# DummyLoadAddOn.net
KiCad netlist of a schematic drawn in Altium Designer
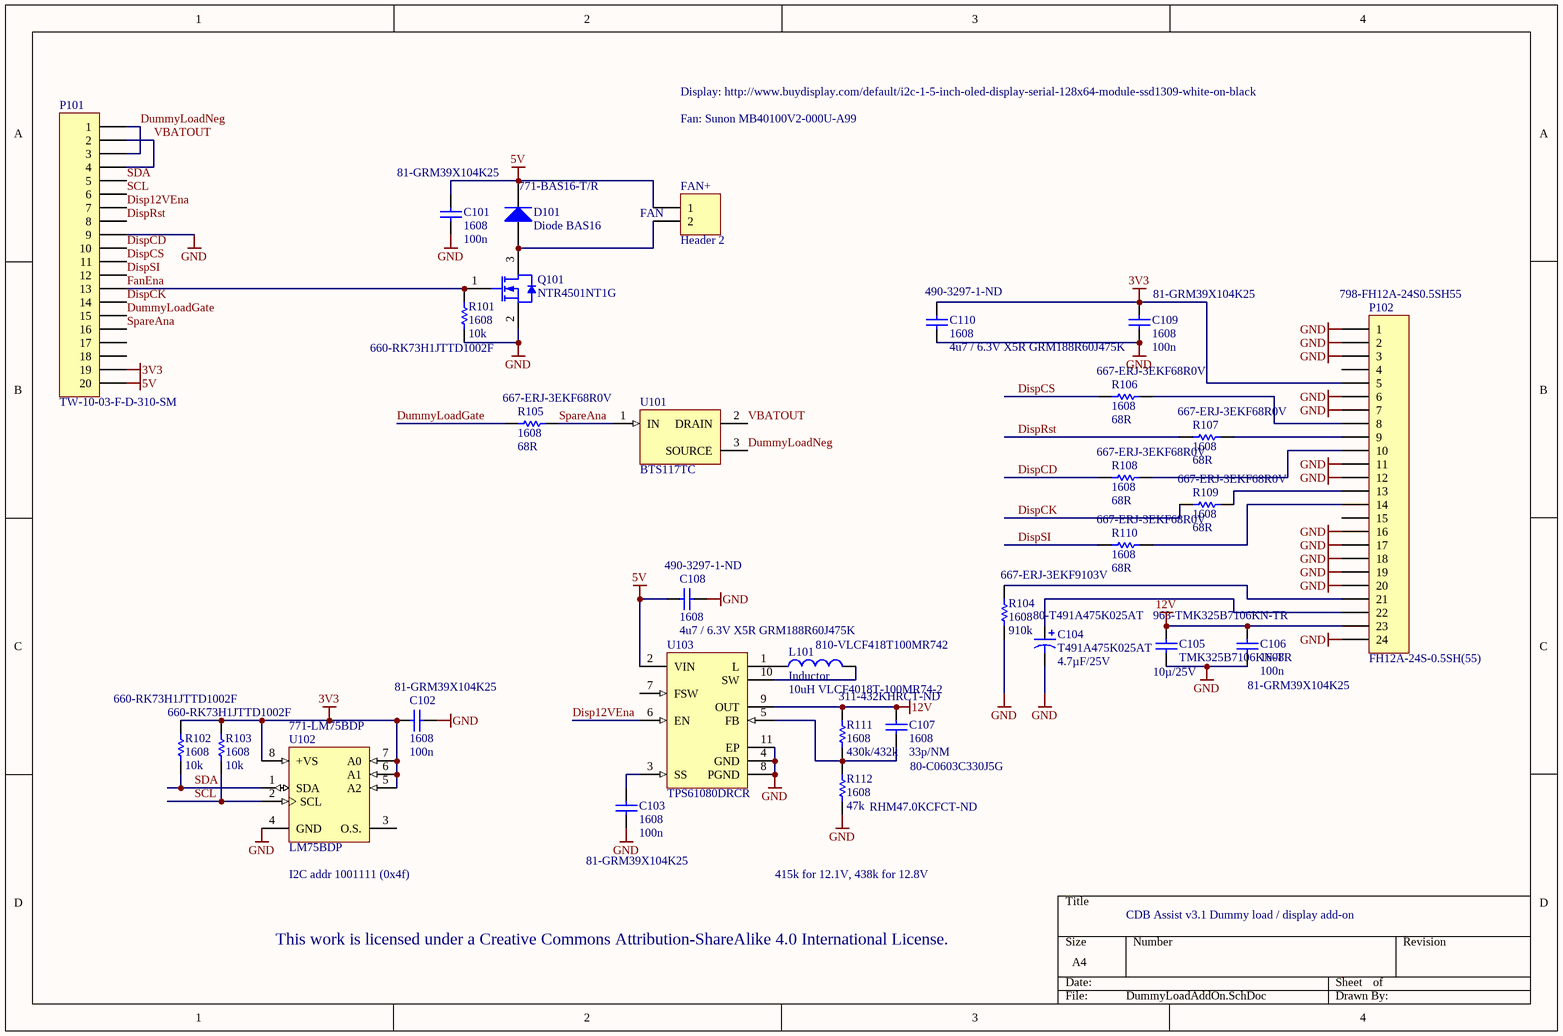
[diagram p0: DummyLoadAddOn.SchDoc]

(export (version "E")
  (design (tool "Eeschema 10.0.6"))
  (components
    (comp (ref "C101")
      (value "1608")
      (footprint "RESC1608N")
      (description "Capacitor (Semiconductor SIM Model)")
      (fields
        (field (name "ALTIUM_VALUE") "100n")
        (field (name "SUPPLIER PART NUMBER 1") "81-GRM39X104K25")
        (field (name "MANUFACTURER") "Murata Electronics")
        (field (name "MANUFACTURER PART NUMBER") "GRM188R71E104KA01D")
        (field (name "PUBLISHER") "Altium Limited")
      )
      (libsource (lib "Miscellaneous Devices") (part "Cap Semi"))
    )
    (comp (ref "C102")
      (value "1608")
      (footprint "RESC1608N")
      (description "Capacitor (Semiconductor SIM Model)")
      (fields
        (field (name "ALTIUM_VALUE") "100n")
        (field (name "SUPPLIER PART NUMBER 1") "81-GRM39X104K25")
        (field (name "MANUFACTURER") "Murata Electronics")
        (field (name "MANUFACTURER PART NUMBER") "GRM188R71E104KA01D")
        (field (name "PUBLISHER") "Altium Limited")
      )
      (libsource (lib "Miscellaneous Devices") (part "Cap Semi"))
    )
    (comp (ref "C103")
      (value "1608")
      (footprint "RESC1608N")
      (description "Capacitor (Semiconductor SIM Model)")
      (fields
        (field (name "ALTIUM_VALUE") "100n")
        (field (name "SUPPLIER PART NUMBER 1") "81-GRM39X104K25")
        (field (name "MANUFACTURER") "Murata Electronics")
        (field (name "MANUFACTURER PART NUMBER") "GRM188R71E104KA01D")
        (field (name "PUBLISHER") "Altium Limited")
      )
      (libsource (lib "Miscellaneous Devices") (part "Cap Semi"))
    )
    (comp (ref "C104")
      (value "T491A475K025AT")
      (footprint "A_3216")
      (description "Solid Tantalum Chip Capacitor, Standard T491 Series - Industrial Grade")
      (fields
        (field (name "ALTIUM_VALUE") "4.7µF/25V")
        (field (name "MANUFACTURER") "Kemet")
        (field (name "SUPPLIER PART NUMBER 1") "80-T491A475K025AT")
        (field (name "TOLERANCE") "10 %")
        (field (name "PUBLISHER") "Altium Limited")
      )
      (libsource (lib "KEMET Chip Capacitor") (part "T491A"))
    )
    (comp (ref "C105")
      (value "TMK325B7106KN-TR")
      (footprint "CAPC3225N")
      (description "Capacitor")
      (fields
        (field (name "ALTIUM_VALUE") "10µ/25V")
        (field (name "SUPPLIER PART NUMBER 1") "963-TMK325B7106KN-TR")
        (field (name "MANUFACTURER") "Taiyo Yuden")
        (field (name "TOLERANCE") "10 %")
        (field (name "PUBLISHER") "Altium Limited")
      )
      (libsource (lib "Miscellaneous Devices") (part "Cap"))
    )
    (comp (ref "C106")
      (value "1608")
      (footprint "RESC1608N")
      (description "Capacitor (Semiconductor SIM Model)")
      (fields
        (field (name "ALTIUM_VALUE") "100n")
        (field (name "SUPPLIER PART NUMBER 1") "81-GRM39X104K25")
        (field (name "MANUFACTURER") "Murata Electronics")
        (field (name "MANUFACTURER PART NUMBER") "GRM188R71E104KA01D")
        (field (name "PUBLISHER") "Altium Limited")
      )
      (libsource (lib "Miscellaneous Devices") (part "Cap Semi"))
    )
    (comp (ref "C107")
      (value "1608")
      (footprint "RESC1608N")
      (description "Capacitor (Semiconductor SIM Model)")
      (fields
        (field (name "ALTIUM_VALUE") "33p/NM")
        (field (name "SUPPLIER PART NUMBER 1") "80-C0603C330J5G")
        (field (name "MANUFACTURER") "Kemet")
        (field (name "MANUFACTURER PART NUMBER") "C0603C330J5GACTU")
        (field (name "PUBLISHER") "Altium Limited")
      )
      (libsource (lib "Miscellaneous Devices") (part "Cap Semi"))
    )
    (comp (ref "C108")
      (value "1608")
      (footprint "RESC1608N")
      (description "Capacitor (Semiconductor SIM Model)")
      (fields
        (field (name "ALTIUM_VALUE") "4u7 / 6.3V X5R GRM188R60J475K")
        (field (name "SUPPLIER PART NUMBER 1") "490-3297-1-ND")
        (field (name "MANUFACTURER") "Murata Electronics North America")
        (field (name "MANUFACTURER PART NUMBER") "GRM188R60J475KE19D")
        (field (name "PUBLISHER") "Altium Limited")
      )
      (libsource (lib "Miscellaneous Devices") (part "Cap Semi"))
    )
    (comp (ref "C109")
      (value "1608")
      (footprint "RESC1608N")
      (description "Capacitor (Semiconductor SIM Model)")
      (fields
        (field (name "ALTIUM_VALUE") "100n")
        (field (name "SUPPLIER PART NUMBER 1") "81-GRM39X104K25")
        (field (name "MANUFACTURER") "Murata Electronics")
        (field (name "MANUFACTURER PART NUMBER") "GRM188R71E104KA01D")
        (field (name "PUBLISHER") "Altium Limited")
      )
      (libsource (lib "Miscellaneous Devices") (part "Cap Semi"))
    )
    (comp (ref "C110")
      (value "1608")
      (footprint "RESC1608N")
      (description "Capacitor (Semiconductor SIM Model)")
      (fields
        (field (name "ALTIUM_VALUE") "4u7 / 6.3V X5R GRM188R60J475K")
        (field (name "SUPPLIER PART NUMBER 1") "490-3297-1-ND")
        (field (name "MANUFACTURER") "Murata Electronics North America")
        (field (name "MANUFACTURER PART NUMBER") "GRM188R60J475KE19D")
        (field (name "PUBLISHER") "Altium Limited")
      )
      (libsource (lib "Miscellaneous Devices") (part "Cap Semi"))
    )
    (comp (ref "D101")
      (value "Diode BAS16")
      (footprint "SOT-23_N")
      (description "Silicon Switching Diode for High-Speed Switching")
      (fields
        (field (name "SUPPLIER PART NUMBER 1") "771-BAS16-T/R")
        (field (name "MANUFACTURER") "NXP Semiconductors")
        (field (name "MANUFACTURER PART NUMBER") "BAS16,215")
        (field (name "PUBLISHER") "Altium Limited")
      )
      (libsource (lib "Miscellaneous Devices") (part "Diode BAS16"))
    )
    (comp (ref "FAN+")
      (value "Header 2")
      (footprint "HDR1X2")
      (description "Header, 2-Pin")
      (fields (field (name "PUBLISHER") "Altium Limited"))
      (libsource (lib "Miscellaneous Connectors") (part "Header 2"))
    )
    (comp (ref "L101")
      (value "Inductor")
      (footprint "SRR4018")
      (fields
        (field (name "ALTIUM_VALUE") "10uH VLCF4018T-100MR74-2")
        (field (name "SUPPLIER PART NUMBER 1") "810-VLCF418T100MR742")
        (field (name "MANUFACTURER") "TDK")
        (field (name "MANUFACTURER PART NUMBER") "VLCF4018T-100MR74-2")
        (field (name "TOLERANCE") "20 %")
        (field (name "PUBLISHER") "Altium Limited")
      )
      (libsource (lib "Miscellaneous Devices") (part "Inductor"))
    )
    (comp (ref "P101")
      (value "TW-10-03-F-D-310-SM")
      (footprint "Samtec TW-SM 20-pin")
      (description "Header, 20-Pin")
      (fields (field (name "PUBLISHER") "Altium Limited"))
      (libsource (lib "Miscellaneous Connectors") (part "Header 20"))
    )
    (comp (ref "P102")
      (value "FH12A-24S-0.5SH(55)")
      (footprint "MI050DXK-24-1 - duplicate")
      (description "FPC 24-pin Display")
      (fields
        (field (name "SUPPLIER PART NUMBER 1") "798-FH12A-24S0.5SH55")
        (field (name "MANUFACTURER") "Hirose Connector")
        (field (name "PUBLISHER") "Altium Limited")
      )
      (libsource (lib "Miscellaneous Connectors") (part "Header 24"))
    )
    (comp (ref "Q101")
      (value "NTR4501NT1G")
      (footprint "ONSC-SOT-23-3-318-08_V")
      (description "Power MOSFET, 20 V, 3.2 A, Single N-Channel, 3-Pin SOT-23, Pb-Free, Tape and Reel")
      (fields (field (name "MANUFACTURER") "On Semiconductor"))
      (libsource (lib "ON Semi MOSFETs") (part "NTR4501NT1G"))
    )
    (comp (ref "R101")
      (value "1608")
      (footprint "RESC1608N")
      (description "Semiconductor Resistor")
      (fields
        (field (name "ALTIUM_VALUE") "10k")
        (field (name "SUPPLIER PART NUMBER 1") "660-RK73H1JTTD1002F")
        (field (name "MANUFACTURER") "KOA Speer")
        (field (name "MANUFACTURER PART NUMBER") "RK73H1JTTD1002F")
        (field (name "PUBLISHER") "Altium Limited")
      )
      (libsource (lib "Miscellaneous Devices") (part "Res Semi"))
    )
    (comp (ref "R102")
      (value "1608")
      (footprint "RESC1608N")
      (description "Semiconductor Resistor")
      (fields
        (field (name "ALTIUM_VALUE") "10k")
        (field (name "SUPPLIER PART NUMBER 1") "660-RK73H1JTTD1002F")
        (field (name "MANUFACTURER") "KOA Speer")
        (field (name "MANUFACTURER PART NUMBER") "RK73H1JTTD1002F")
        (field (name "PUBLISHER") "Altium Limited")
      )
      (libsource (lib "Miscellaneous Devices") (part "Res Semi"))
    )
    (comp (ref "R103")
      (value "1608")
      (footprint "RESC1608N")
      (description "Semiconductor Resistor")
      (fields
        (field (name "ALTIUM_VALUE") "10k")
        (field (name "SUPPLIER PART NUMBER 1") "660-RK73H1JTTD1002F")
        (field (name "MANUFACTURER") "KOA Speer")
        (field (name "MANUFACTURER PART NUMBER") "RK73H1JTTD1002F")
        (field (name "PUBLISHER") "Altium Limited")
      )
      (libsource (lib "Miscellaneous Devices") (part "Res Semi"))
    )
    (comp (ref "R104")
      (value "1608")
      (footprint "RESC1608N")
      (description "Semiconductor Resistor")
      (fields
        (field (name "ALTIUM_VALUE") "910k")
        (field (name "SUPPLIER PART NUMBER 1") "667-ERJ-3EKF9103V")
        (field (name "MANUFACTURER") "Panasonic")
        (field (name "MANUFACTURER PART NUMBER") "ERJ-3EKF9103V")
        (field (name "PUBLISHER") "Altium Limited")
      )
      (libsource (lib "Miscellaneous Devices") (part "Res Semi"))
    )
    (comp (ref "R105")
      (value "1608")
      (footprint "RESC1608N")
      (description "Semiconductor Resistor")
      (fields
        (field (name "ALTIUM_VALUE") "68R")
        (field (name "SUPPLIER PART NUMBER 1") "667-ERJ-3EKF68R0V")
        (field (name "MANUFACTURER") "Panasonic")
        (field (name "MANUFACTURER PART NUMBER") "ERJ-3EKF68R0V")
        (field (name "PUBLISHER") "Altium Limited")
      )
      (libsource (lib "Miscellaneous Devices") (part "Res Semi"))
    )
    (comp (ref "R106")
      (value "1608")
      (footprint "RESC1608N")
      (description "Semiconductor Resistor")
      (fields
        (field (name "ALTIUM_VALUE") "68R")
        (field (name "SUPPLIER PART NUMBER 1") "667-ERJ-3EKF68R0V")
        (field (name "MANUFACTURER") "Panasonic")
        (field (name "MANUFACTURER PART NUMBER") "ERJ-3EKF68R0V")
        (field (name "PUBLISHER") "Altium Limited")
      )
      (libsource (lib "Miscellaneous Devices") (part "Res Semi"))
    )
    (comp (ref "R107")
      (value "1608")
      (footprint "RESC1608N")
      (description "Semiconductor Resistor")
      (fields
        (field (name "ALTIUM_VALUE") "68R")
        (field (name "SUPPLIER PART NUMBER 1") "667-ERJ-3EKF68R0V")
        (field (name "MANUFACTURER") "Panasonic")
        (field (name "MANUFACTURER PART NUMBER") "ERJ-3EKF68R0V")
        (field (name "PUBLISHER") "Altium Limited")
      )
      (libsource (lib "Miscellaneous Devices") (part "Res Semi"))
    )
    (comp (ref "R108")
      (value "1608")
      (footprint "RESC1608N")
      (description "Semiconductor Resistor")
      (fields
        (field (name "ALTIUM_VALUE") "68R")
        (field (name "SUPPLIER PART NUMBER 1") "667-ERJ-3EKF68R0V")
        (field (name "MANUFACTURER") "Panasonic")
        (field (name "MANUFACTURER PART NUMBER") "ERJ-3EKF68R0V")
        (field (name "PUBLISHER") "Altium Limited")
      )
      (libsource (lib "Miscellaneous Devices") (part "Res Semi"))
    )
    (comp (ref "R109")
      (value "1608")
      (footprint "RESC1608N")
      (description "Semiconductor Resistor")
      (fields
        (field (name "ALTIUM_VALUE") "68R")
        (field (name "SUPPLIER PART NUMBER 1") "667-ERJ-3EKF68R0V")
        (field (name "MANUFACTURER") "Panasonic")
        (field (name "MANUFACTURER PART NUMBER") "ERJ-3EKF68R0V")
        (field (name "PUBLISHER") "Altium Limited")
      )
      (libsource (lib "Miscellaneous Devices") (part "Res Semi"))
    )
    (comp (ref "R110")
      (value "1608")
      (footprint "RESC1608N")
      (description "Semiconductor Resistor")
      (fields
        (field (name "ALTIUM_VALUE") "68R")
        (field (name "SUPPLIER PART NUMBER 1") "667-ERJ-3EKF68R0V")
        (field (name "MANUFACTURER") "Panasonic")
        (field (name "MANUFACTURER PART NUMBER") "ERJ-3EKF68R0V")
        (field (name "PUBLISHER") "Altium Limited")
      )
      (libsource (lib "Miscellaneous Devices") (part "Res Semi"))
    )
    (comp (ref "R111")
      (value "1608")
      (footprint "RESC1608N")
      (description "Semiconductor Resistor")
      (fields
        (field (name "ALTIUM_VALUE") "430k/432k")
        (field (name "SUPPLIER PART NUMBER 1") "311-432KHRCT-ND")
        (field (name "MANUFACTURER") "Yageo")
        (field (name "MANUFACTURER PART NUMBER") "RC0603FR-07432KL")
        (field (name "PUBLISHER") "Altium Limited")
      )
      (libsource (lib "Miscellaneous Devices") (part "Res Semi"))
    )
    (comp (ref "R112")
      (value "1608")
      (footprint "RESC1608N")
      (description "Semiconductor Resistor")
      (fields
        (field (name "ALTIUM_VALUE") "47k")
        (field (name "SUPPLIER PART NUMBER 1") "RHM47.0KCFCT-ND")
        (field (name "MANUFACTURER") "Rohm Semiconductor")
        (field (name "MANUFACTURER PART NUMBER") "MCR03ERTF4702")
        (field (name "PUBLISHER") "Altium Limited")
      )
      (libsource (lib "Miscellaneous Devices") (part "Res Semi"))
    )
    (comp (ref "U101")
      (value "BTS117TC")
      (footprint "INF-PG-TO263-3-2_N")
      (description "Smart Low-Side Power Switch HITFET, 60 V VDS, 3.5 A ID, -40 to 150 degC, PG-TO263-3-2, Reel, Green")
      (fields (field (name "MANUFACTURER") "Infineon"))
      (libsource (lib "BTS117TC") (part "BTS117TC"))
    )
    (comp (ref "U102")
      (value "LM75BDP")
      (footprint "MUA08A_N")
      (description "Digital Temperature Sensor and Thermal Watchdog with Two-Wire Interface, 8-pin Mini SOIC, Pb-Free")
      (fields
        (field (name "PARTNUMBER") "LM75BIMM-3/NOPB")
        (field (name "MANUFACTURER") "National Semiconductor")
        (field (name "SUPPLIER PART NUMBER 1") "771-LM75BDP")
      )
      (libsource (lib "National Semiconductor Temperature Sensor") (part "LM75BIMM-3/NOPB"))
    )
    (comp (ref "U103")
      (value "TPS61080DRCR")
      (footprint "TI-DRC10-2400X1650TP_V")
      (fields (field (name "MANUFACTURER") "Texas Instruments"))
      (libsource (lib "TI Power Management Lighting and Display") (part "TPS61080DRCR"))
    )
  )
  (nets
    (net (code "1") (name "/Disp12VEna") (class "Default")
      (node (ref "P101") (pin "7") (pinfunction "7_7") (pintype "passive"))
      (node (ref "U103") (pin "6") (pinfunction "EN_6") (pintype "input"))
    )
    (net (code "2") (name "/DispCD") (class "Default")
      (node (ref "P101") (pin "10") (pinfunction "10_10") (pintype "passive"))
      (node (ref "R108") (pin "2") (pinfunction "2_2") (pintype "passive"))
    )
    (net (code "3") (name "/DispCK") (class "Default")
      (node (ref "P101") (pin "14") (pinfunction "14_14") (pintype "passive"))
      (node (ref "R109") (pin "2") (pinfunction "2_2") (pintype "passive"))
    )
    (net (code "4") (name "/DispCS") (class "Default")
      (node (ref "P101") (pin "11") (pinfunction "11_11") (pintype "passive"))
      (node (ref "R106") (pin "2") (pinfunction "2_2") (pintype "passive"))
    )
    (net (code "5") (name "/DispRst") (class "Default")
      (node (ref "P101") (pin "8") (pinfunction "8_8") (pintype "passive"))
      (node (ref "R107") (pin "2") (pinfunction "2_2") (pintype "passive"))
    )
    (net (code "6") (name "/DispSI") (class "Default")
      (node (ref "P101") (pin "12") (pinfunction "12_12") (pintype "passive"))
      (node (ref "R110") (pin "2") (pinfunction "2_2") (pintype "passive"))
    )
    (net (code "7") (name "/DummyLoadGate") (class "Default")
      (node (ref "P101") (pin "15") (pinfunction "15_15") (pintype "passive"))
      (node (ref "R105") (pin "2") (pinfunction "2_2") (pintype "passive"))
    )
    (net (code "8") (name "/DummyLoadNeg") (class "Default")
      (node (ref "P101") (pin "1") (pinfunction "1_1") (pintype "passive"))
      (node (ref "P101") (pin "3") (pinfunction "3_3") (pintype "passive"))
      (node (ref "U101") (pin "3") (pinfunction "SOURCE_3") (pintype "power_in"))
    )
    (net (code "9") (name "/FanEna") (class "Default")
      (node (ref "P101") (pin "13") (pinfunction "13_13") (pintype "passive"))
      (node (ref "Q101") (pin "1") (pinfunction "G_1") (pintype "passive"))
      (node (ref "R101") (pin "2") (pinfunction "2_2") (pintype "passive"))
    )
    (net (code "10") (name "/SCL") (class "Default")
      (node (ref "P101") (pin "6") (pinfunction "6_6") (pintype "passive"))
      (node (ref "R103") (pin "1") (pinfunction "1_1") (pintype "passive"))
      (node (ref "U102") (pin "2") (pinfunction "SCL_2") (pintype "input"))
    )
    (net (code "11") (name "/SDA") (class "Default")
      (node (ref "P101") (pin "5") (pinfunction "5_5") (pintype "passive"))
      (node (ref "R102") (pin "1") (pinfunction "1_1") (pintype "passive"))
      (node (ref "U102") (pin "1") (pinfunction "SDA_1") (pintype "bidirectional"))
    )
    (net (code "12") (name "/SpareAna") (class "Default")
      (node (ref "P101") (pin "16") (pinfunction "16_16") (pintype "passive"))
      (node (ref "R105") (pin "1") (pinfunction "1_1") (pintype "passive"))
      (node (ref "U101") (pin "1") (pinfunction "IN_1") (pintype "input"))
    )
    (net (code "13") (name "/VBATOUT") (class "Default")
      (node (ref "P101") (pin "2") (pinfunction "2_2") (pintype "passive"))
      (node (ref "P101") (pin "4") (pinfunction "4_4") (pintype "passive"))
      (node (ref "U101") (pin "2") (pinfunction "DRAIN_2") (pintype "power_in"))
    )
    (net (code "14") (name "3V3") (class "Default")
      (node (ref "C102") (pin "2") (pinfunction "2_2") (pintype "passive"))
      (node (ref "C109") (pin "1") (pinfunction "1_1") (pintype "passive"))
      (node (ref "C110") (pin "1") (pinfunction "1_1") (pintype "passive"))
      (node (ref "P101") (pin "19") (pinfunction "19_19") (pintype "passive"))
      (node (ref "P102") (pin "5") (pinfunction "5_5") (pintype "passive"))
      (node (ref "R102") (pin "2") (pinfunction "2_2") (pintype "passive"))
      (node (ref "R103") (pin "2") (pinfunction "2_2") (pintype "passive"))
      (node (ref "U102") (pin "5") (pinfunction "A2_5") (pintype "input"))
      (node (ref "U102") (pin "6") (pinfunction "A1_6") (pintype "input"))
      (node (ref "U102") (pin "7") (pinfunction "A0_7") (pintype "input"))
      (node (ref "U102") (pin "8") (pinfunction "+VS_8") (pintype "input"))
    )
    (net (code "15") (name "5V") (class "Default")
      (node (ref "C101") (pin "2") (pinfunction "2_2") (pintype "passive"))
      (node (ref "C108") (pin "2") (pinfunction "2_2") (pintype "passive"))
      (node (ref "D101") (pin "3") (pinfunction "K_3") (pintype "passive"))
      (node (ref "FAN+") (pin "1") (pinfunction "1_1") (pintype "passive"))
      (node (ref "P101") (pin "20") (pinfunction "20_20") (pintype "passive"))
      (node (ref "U103") (pin "2") (pinfunction "VIN_2") (pintype "power_in"))
    )
    (net (code "16") (name "12V") (class "Default")
      (node (ref "C105") (pin "1") (pinfunction "1_1") (pintype "passive"))
      (node (ref "C106") (pin "2") (pinfunction "2_2") (pintype "passive"))
      (node (ref "C107") (pin "2") (pinfunction "2_2") (pintype "passive"))
      (node (ref "P102") (pin "23") (pinfunction "23_23") (pintype "passive"))
      (node (ref "R111") (pin "1") (pinfunction "1_1") (pintype "passive"))
      (node (ref "U103") (pin "9") (pinfunction "OUT_9") (pintype "power_in"))
    )
    (net (code "17") (name "GND") (class "Default")
      (node (ref "C101") (pin "1") (pinfunction "1_1") (pintype "passive"))
      (node (ref "C102") (pin "1") (pinfunction "1_1") (pintype "passive"))
      (node (ref "C103") (pin "1") (pinfunction "1_1") (pintype "passive"))
      (node (ref "C104") (pin "2") (pinfunction "2_2") (pintype "passive"))
      (node (ref "C105") (pin "2") (pinfunction "2_2") (pintype "passive"))
      (node (ref "C106") (pin "1") (pinfunction "1_1") (pintype "passive"))
      (node (ref "C108") (pin "1") (pinfunction "1_1") (pintype "passive"))
      (node (ref "C109") (pin "2") (pinfunction "2_2") (pintype "passive"))
      (node (ref "C110") (pin "2") (pinfunction "2_2") (pintype "passive"))
      (node (ref "P101") (pin "9") (pinfunction "9_9") (pintype "passive"))
      (node (ref "P102") (pin "1") (pinfunction "1_1") (pintype "passive"))
      (node (ref "P102") (pin "11") (pinfunction "11_11") (pintype "passive"))
      (node (ref "P102") (pin "12") (pinfunction "12_12") (pintype "passive"))
      (node (ref "P102") (pin "16") (pinfunction "16_16") (pintype "passive"))
      (node (ref "P102") (pin "17") (pinfunction "17_17") (pintype "passive"))
      (node (ref "P102") (pin "18") (pinfunction "18_18") (pintype "passive"))
      (node (ref "P102") (pin "19") (pinfunction "19_19") (pintype "passive"))
      (node (ref "P102") (pin "2") (pinfunction "2_2") (pintype "passive"))
      (node (ref "P102") (pin "20") (pinfunction "20_20") (pintype "passive"))
      (node (ref "P102") (pin "24") (pinfunction "24_24") (pintype "passive"))
      (node (ref "P102") (pin "3") (pinfunction "3_3") (pintype "passive"))
      (node (ref "P102") (pin "6") (pinfunction "6_6") (pintype "passive"))
      (node (ref "P102") (pin "7") (pinfunction "7_7") (pintype "passive"))
      (node (ref "Q101") (pin "2") (pinfunction "S_2") (pintype "passive"))
      (node (ref "R101") (pin "1") (pinfunction "1_1") (pintype "passive"))
      (node (ref "R104") (pin "2") (pinfunction "2_2") (pintype "passive"))
      (node (ref "R112") (pin "2") (pinfunction "2_2") (pintype "passive"))
      (node (ref "U102") (pin "4") (pinfunction "GND_4") (pintype "power_in"))
      (node (ref "U103") (pin "11") (pinfunction "EP_11") (pintype "power_in"))
      (node (ref "U103") (pin "4") (pinfunction "GND_4") (pintype "power_in"))
      (node (ref "U103") (pin "8") (pinfunction "PGND_8") (pintype "power_in"))
    )
    (net (code "18") (name "Net-(C104-Pad1)") (class "Default")
      (node (ref "C104") (pin "1") (pinfunction "1_1") (pintype "passive"))
      (node (ref "P102") (pin "22") (pinfunction "22_22") (pintype "passive"))
    )
    (net (code "19") (name "Net-(D101-A)") (class "Default")
      (node (ref "D101") (pin "1") (pinfunction "A_1") (pintype "passive"))
      (node (ref "FAN+") (pin "2") (pinfunction "2_2") (pintype "passive"))
      (node (ref "Q101") (pin "3") (pinfunction "D_3") (pintype "passive"))
    )
    (net (code "20") (name "Net-(P102-Pad8)") (class "Default")
      (node (ref "P102") (pin "8") (pinfunction "8_8") (pintype "passive"))
      (node (ref "R106") (pin "1") (pinfunction "1_1") (pintype "passive"))
    )
    (net (code "21") (name "Net-(P102-Pad9)") (class "Default")
      (node (ref "P102") (pin "9") (pinfunction "9_9") (pintype "passive"))
      (node (ref "R107") (pin "1") (pinfunction "1_1") (pintype "passive"))
    )
    (net (code "22") (name "Net-(P102-Pad10)") (class "Default")
      (node (ref "P102") (pin "10") (pinfunction "10_10") (pintype "passive"))
      (node (ref "R108") (pin "1") (pinfunction "1_1") (pintype "passive"))
    )
    (net (code "23") (name "Net-(P102-Pad13)") (class "Default")
      (node (ref "P102") (pin "13") (pinfunction "13_13") (pintype "passive"))
      (node (ref "R109") (pin "1") (pinfunction "1_1") (pintype "passive"))
    )
    (net (code "24") (name "Net-(P102-Pad14)") (class "Default")
      (node (ref "P102") (pin "14") (pinfunction "14_14") (pintype "passive"))
      (node (ref "R110") (pin "1") (pinfunction "1_1") (pintype "passive"))
    )
    (net (code "25") (name "Net-(P102-Pad21)") (class "Default")
      (node (ref "P102") (pin "21") (pinfunction "21_21") (pintype "passive"))
      (node (ref "R104") (pin "1") (pinfunction "1_1") (pintype "passive"))
    )
    (net (code "26") (name "Net-(U103-FB)") (class "Default")
      (node (ref "C107") (pin "1") (pinfunction "1_1") (pintype "passive"))
      (node (ref "R111") (pin "2") (pinfunction "2_2") (pintype "passive"))
      (node (ref "R112") (pin "1") (pinfunction "1_1") (pintype "passive"))
      (node (ref "U103") (pin "5") (pinfunction "FB_5") (pintype "input"))
    )
    (net (code "27") (name "Net-(U103-L)") (class "Default")
      (node (ref "L101") (pin "1") (pinfunction "1_1") (pintype "passive"))
      (node (ref "U103") (pin "1") (pinfunction "L_1") (pintype "power_in"))
    )
    (net (code "28") (name "Net-(U103-SS)") (class "Default")
      (node (ref "C103") (pin "2") (pinfunction "2_2") (pintype "passive"))
      (node (ref "U103") (pin "3") (pinfunction "SS_3") (pintype "input"))
    )
    (net (code "29") (name "Net-(U103-SW)") (class "Default")
      (node (ref "L101") (pin "2") (pinfunction "2_2") (pintype "passive"))
      (node (ref "U103") (pin "10") (pinfunction "SW_10") (pintype "power_in"))
    )
    (net (code "30") (name "unconnected-(P101-Pad17)") (class "Default")
      (node (ref "P101") (pin "17") (pinfunction "17_17") (pintype "passive"))
    )
    (net (code "31") (name "unconnected-(P101-Pad18)") (class "Default")
      (node (ref "P101") (pin "18") (pinfunction "18_18") (pintype "passive"))
    )
    (net (code "32") (name "unconnected-(P102-Pad4)") (class "Default")
      (node (ref "P102") (pin "4") (pinfunction "4_4") (pintype "passive"))
    )
    (net (code "33") (name "unconnected-(P102-Pad15)") (class "Default")
      (node (ref "P102") (pin "15") (pinfunction "15_15") (pintype "passive"))
    )
    (net (code "34") (name "unconnected-(U102-O.S.-Pad3)") (class "Default")
      (node (ref "U102") (pin "3") (pinfunction "O.S._3") (pintype "open_collector"))
    )
    (net (code "35") (name "unconnected-(U103-FSW-Pad7)") (class "Default")
      (node (ref "U103") (pin "7") (pinfunction "FSW_7") (pintype "input"))
    )
  )
)
